# f1c200s_V1_0.net
KiCad netlist of a schematic drawn in EasyEDA Pro
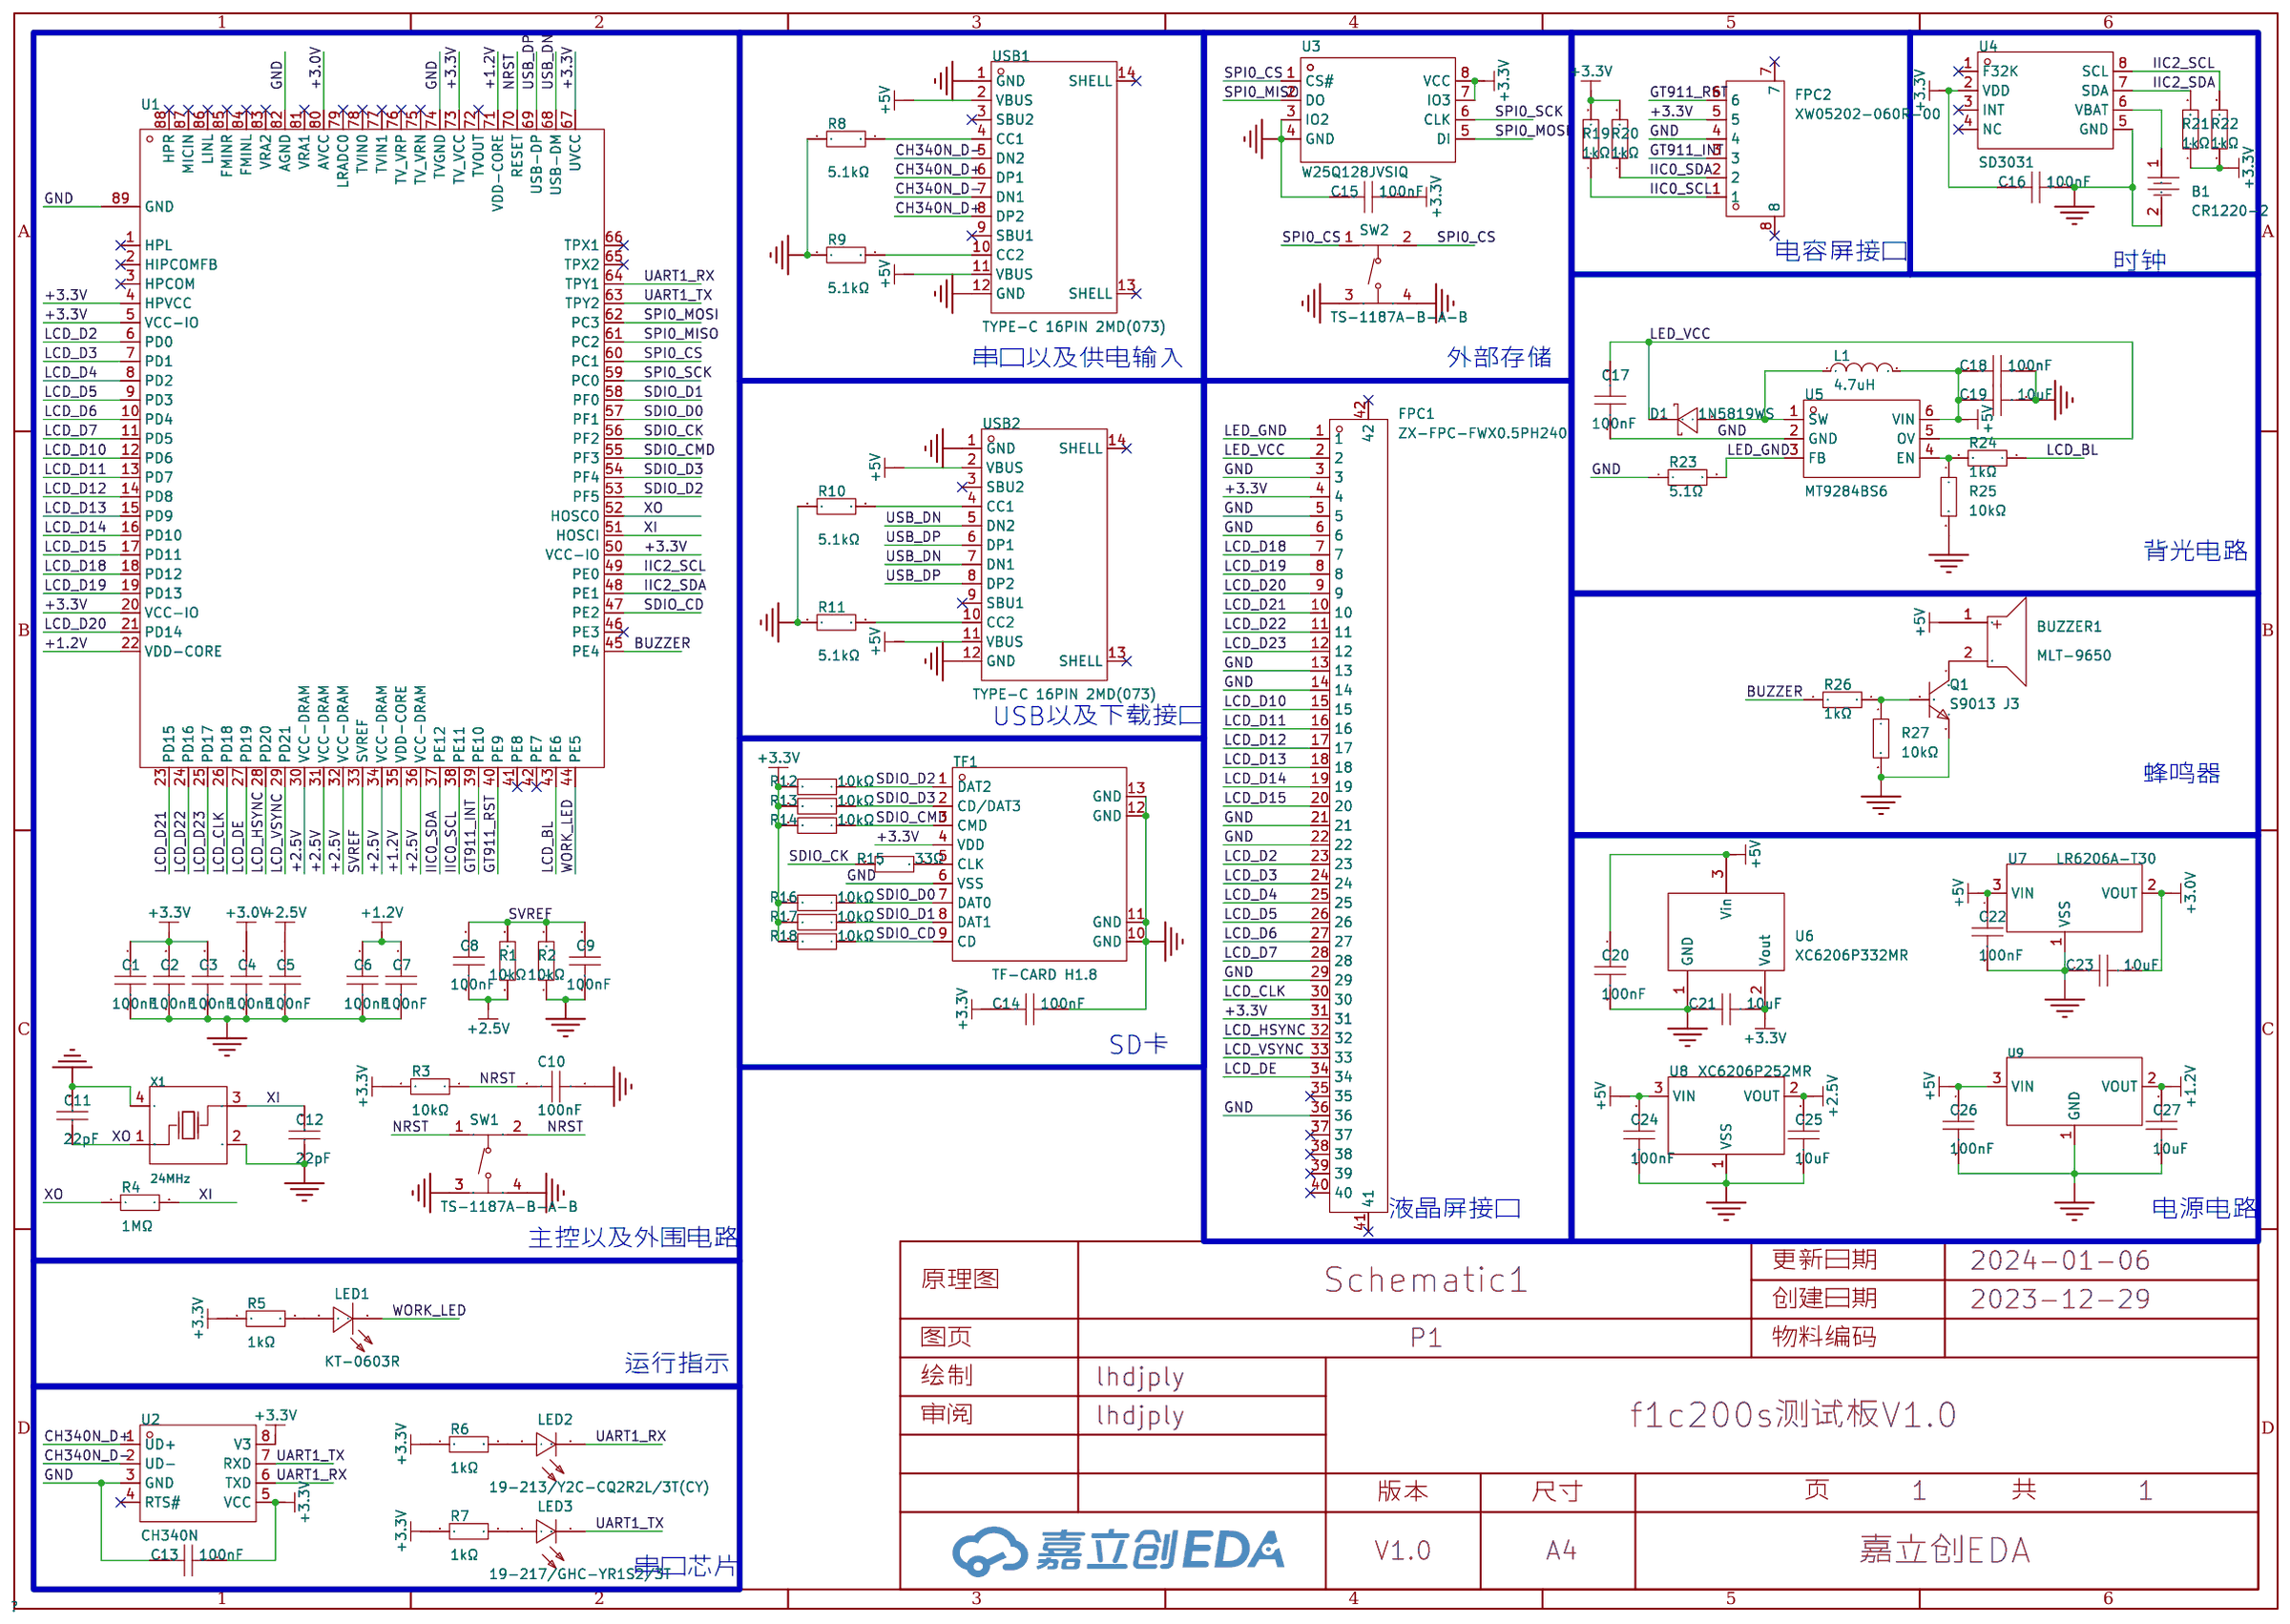
[diagram p0: schematic sheet]

(export (version "E")
  (design (tool "Eeschema 10.0.6"))
  (components
    (comp (ref "B1")
      (value "CR1220-2")
      (footprint "easyedapro:BAT-SMD_CR1220-2")
      (description "连接器类型:电池底座;适用电池规格:CR1220;工作温度范围:-;")
      (fields (field (name "Manufacturer") "Q&amp;J"))
      (libsource (lib "easyedapro") (part "CR1220-2"))
    )
    (comp (ref "BUZZER1")
      (value "2700Hz")
      (footprint "easyedapro:BUZ-SMD_L9.6-W9.6-LS10.0-R")
      (fields (field (name "Manufacturer Part") "MLT-9650") (field (name "Manufacturer") "华能"))
      (libsource (lib "easyedapro") (part "HND-9650B"))
    )
    (comp (ref "C1")
      (value "100nF")
      (footprint "easyedapro:C0603")
      (description "容值:100nF;精度:±10%;额定电压:50V;材质(温度系数):X7R;")
      (fields
        (field (name "Manufacturer Part") "CC0603KRX7R9BB104")
        (field (name "Manufacturer") "YAGEO(国巨)")
      )
      (libsource (lib "easyedapro") (part "CC0603KRX7R9BB104"))
    )
    (comp (ref "C2")
      (value "100nF")
      (footprint "easyedapro:C0603")
      (description "容值:100nF;精度:±10%;额定电压:50V;材质(温度系数):X7R;")
      (fields
        (field (name "Manufacturer Part") "CC0603KRX7R9BB104")
        (field (name "Manufacturer") "YAGEO(国巨)")
      )
      (libsource (lib "easyedapro") (part "CC0603KRX7R9BB104"))
    )
    (comp (ref "C3")
      (value "100nF")
      (footprint "easyedapro:C0603")
      (description "容值:100nF;精度:±10%;额定电压:50V;材质(温度系数):X7R;")
      (fields
        (field (name "Manufacturer Part") "CC0603KRX7R9BB104")
        (field (name "Manufacturer") "YAGEO(国巨)")
      )
      (libsource (lib "easyedapro") (part "CC0603KRX7R9BB104"))
    )
    (comp (ref "C4")
      (value "100nF")
      (footprint "easyedapro:C0603")
      (description "容值:100nF;精度:±10%;额定电压:50V;材质(温度系数):X7R;")
      (fields
        (field (name "Manufacturer Part") "CC0603KRX7R9BB104")
        (field (name "Manufacturer") "YAGEO(国巨)")
      )
      (libsource (lib "easyedapro") (part "CC0603KRX7R9BB104"))
    )
    (comp (ref "C5")
      (value "100nF")
      (footprint "easyedapro:C0603")
      (description "容值:100nF;精度:±10%;额定电压:50V;材质(温度系数):X7R;")
      (fields
        (field (name "Manufacturer Part") "CC0603KRX7R9BB104")
        (field (name "Manufacturer") "YAGEO(国巨)")
      )
      (libsource (lib "easyedapro") (part "CC0603KRX7R9BB104"))
    )
    (comp (ref "C6")
      (value "100nF")
      (footprint "easyedapro:C0603")
      (description "容值:100nF;精度:±10%;额定电压:50V;材质(温度系数):X7R;")
      (fields
        (field (name "Manufacturer Part") "CC0603KRX7R9BB104")
        (field (name "Manufacturer") "YAGEO(国巨)")
      )
      (libsource (lib "easyedapro") (part "CC0603KRX7R9BB104"))
    )
    (comp (ref "C7")
      (value "100nF")
      (footprint "easyedapro:C0603")
      (description "容值:100nF;精度:±10%;额定电压:50V;材质(温度系数):X7R;")
      (fields
        (field (name "Manufacturer Part") "CC0603KRX7R9BB104")
        (field (name "Manufacturer") "YAGEO(国巨)")
      )
      (libsource (lib "easyedapro") (part "CC0603KRX7R9BB104"))
    )
    (comp (ref "C8")
      (value "100nF")
      (footprint "easyedapro:C0603")
      (description "容值:100nF;精度:±10%;额定电压:50V;材质(温度系数):X7R;")
      (fields
        (field (name "Manufacturer Part") "CC0603KRX7R9BB104")
        (field (name "Manufacturer") "YAGEO(国巨)")
      )
      (libsource (lib "easyedapro") (part "CC0603KRX7R9BB104"))
    )
    (comp (ref "C9")
      (value "100nF")
      (footprint "easyedapro:C0603")
      (description "容值:100nF;精度:±10%;额定电压:50V;材质(温度系数):X7R;")
      (fields
        (field (name "Manufacturer Part") "CC0603KRX7R9BB104")
        (field (name "Manufacturer") "YAGEO(国巨)")
      )
      (libsource (lib "easyedapro") (part "CC0603KRX7R9BB104"))
    )
    (comp (ref "C10")
      (value "100nF")
      (footprint "easyedapro:C0603")
      (description "容值:100nF;精度:±10%;额定电压:50V;材质(温度系数):X7R;")
      (fields
        (field (name "Manufacturer Part") "CC0603KRX7R9BB104")
        (field (name "Manufacturer") "YAGEO(国巨)")
      )
      (libsource (lib "easyedapro") (part "CC0603KRX7R9BB104"))
    )
    (comp (ref "C11")
      (value "22pF")
      (footprint "easyedapro:C0603")
      (description "容值:22pF;精度:±5%;额定电压:50V;材质(温度系数):C0G;")
      (fields
        (field (name "Manufacturer Part") "CL10C220JB8NNNC")
        (field (name "Manufacturer") "SAMSUNG(三星)")
      )
      (libsource (lib "easyedapro") (part "CL10C220JB8NNNC"))
    )
    (comp (ref "C12")
      (value "22pF")
      (footprint "easyedapro:C0603")
      (description "容值:22pF;精度:±5%;额定电压:50V;材质(温度系数):C0G;")
      (fields
        (field (name "Manufacturer Part") "CL10C220JB8NNNC")
        (field (name "Manufacturer") "SAMSUNG(三星)")
      )
      (libsource (lib "easyedapro") (part "CL10C220JB8NNNC"))
    )
    (comp (ref "C13")
      (value "100nF")
      (footprint "easyedapro:C0603")
      (description "容值:100nF;精度:±10%;额定电压:50V;材质(温度系数):X7R;")
      (fields
        (field (name "Manufacturer Part") "CC0603KRX7R9BB104")
        (field (name "Manufacturer") "YAGEO(国巨)")
      )
      (libsource (lib "easyedapro") (part "CC0603KRX7R9BB104"))
    )
    (comp (ref "C14")
      (value "100nF")
      (footprint "easyedapro:C0603")
      (description "容值:100nF;精度:±10%;额定电压:50V;材质(温度系数):X7R;")
      (fields
        (field (name "Manufacturer Part") "CC0603KRX7R9BB104")
        (field (name "Manufacturer") "YAGEO(国巨)")
      )
      (libsource (lib "easyedapro") (part "CC0603KRX7R9BB104"))
    )
    (comp (ref "C15")
      (value "100nF")
      (footprint "easyedapro:C0603")
      (description "容值:100nF;精度:±10%;额定电压:50V;材质(温度系数):X7R;")
      (fields
        (field (name "Manufacturer Part") "CC0603KRX7R9BB104")
        (field (name "Manufacturer") "YAGEO(国巨)")
      )
      (libsource (lib "easyedapro") (part "CC0603KRX7R9BB104"))
    )
    (comp (ref "C16")
      (value "100nF")
      (footprint "easyedapro:C0603")
      (description "容值:100nF;精度:±10%;额定电压:50V;材质(温度系数):X7R;")
      (fields
        (field (name "Manufacturer Part") "CC0603KRX7R9BB104")
        (field (name "Manufacturer") "YAGEO(国巨)")
      )
      (libsource (lib "easyedapro") (part "CC0603KRX7R9BB104"))
    )
    (comp (ref "C17")
      (value "100nF")
      (footprint "easyedapro:C0603")
      (description "容值:100nF;精度:±10%;额定电压:50V;材质(温度系数):X7R;")
      (fields
        (field (name "Manufacturer Part") "CC0603KRX7R9BB104")
        (field (name "Manufacturer") "YAGEO(国巨)")
      )
      (libsource (lib "easyedapro") (part "CC0603KRX7R9BB104"))
    )
    (comp (ref "C18")
      (value "100nF")
      (footprint "easyedapro:C0603")
      (description "容值:100nF;精度:±10%;额定电压:50V;材质(温度系数):X7R;")
      (fields
        (field (name "Manufacturer Part") "CC0603KRX7R9BB104")
        (field (name "Manufacturer") "YAGEO(国巨)")
      )
      (libsource (lib "easyedapro") (part "CC0603KRX7R9BB104"))
    )
    (comp (ref "C19")
      (value "10uF")
      (footprint "easyedapro:C0603")
      (description "容值:10uF;精度:±10%;额定电压:10V;材质(温度系数):X5R;")
      (fields
        (field (name "Manufacturer Part") "CL10A106KP8NNNC")
        (field (name "Manufacturer") "SAMSUNG(三星)")
      )
      (libsource (lib "easyedapro") (part "CL10A106KP8NNNC"))
    )
    (comp (ref "C20")
      (value "100nF")
      (footprint "easyedapro:C0603")
      (description "容值:100nF;精度:±10%;额定电压:50V;材质(温度系数):X7R;")
      (fields
        (field (name "Manufacturer Part") "CC0603KRX7R9BB104")
        (field (name "Manufacturer") "YAGEO(国巨)")
      )
      (libsource (lib "easyedapro") (part "CC0603KRX7R9BB104"))
    )
    (comp (ref "C21")
      (value "10uF")
      (footprint "easyedapro:C0603")
      (description "容值:10uF;精度:±10%;额定电压:10V;材质(温度系数):X5R;")
      (fields
        (field (name "Manufacturer Part") "CL10A106KP8NNNC")
        (field (name "Manufacturer") "SAMSUNG(三星)")
      )
      (libsource (lib "easyedapro") (part "CL10A106KP8NNNC"))
    )
    (comp (ref "C22")
      (value "100nF")
      (footprint "easyedapro:C0603")
      (description "容值:100nF;精度:±10%;额定电压:50V;材质(温度系数):X7R;")
      (fields
        (field (name "Manufacturer Part") "CC0603KRX7R9BB104")
        (field (name "Manufacturer") "YAGEO(国巨)")
      )
      (libsource (lib "easyedapro") (part "CC0603KRX7R9BB104"))
    )
    (comp (ref "C23")
      (value "10uF")
      (footprint "easyedapro:C0603")
      (description "容值:10uF;精度:±10%;额定电压:10V;材质(温度系数):X5R;")
      (fields
        (field (name "Manufacturer Part") "CL10A106KP8NNNC")
        (field (name "Manufacturer") "SAMSUNG(三星)")
      )
      (libsource (lib "easyedapro") (part "CL10A106KP8NNNC"))
    )
    (comp (ref "C24")
      (value "100nF")
      (footprint "easyedapro:C0603")
      (description "容值:100nF;精度:±10%;额定电压:50V;材质(温度系数):X7R;")
      (fields
        (field (name "Manufacturer Part") "CC0603KRX7R9BB104")
        (field (name "Manufacturer") "YAGEO(国巨)")
      )
      (libsource (lib "easyedapro") (part "CC0603KRX7R9BB104"))
    )
    (comp (ref "C25")
      (value "10uF")
      (footprint "easyedapro:C0603")
      (description "容值:10uF;精度:±10%;额定电压:10V;材质(温度系数):X5R;")
      (fields
        (field (name "Manufacturer Part") "CL10A106KP8NNNC")
        (field (name "Manufacturer") "SAMSUNG(三星)")
      )
      (libsource (lib "easyedapro") (part "CL10A106KP8NNNC"))
    )
    (comp (ref "C26")
      (value "100nF")
      (footprint "easyedapro:C0603")
      (description "容值:100nF;精度:±10%;额定电压:50V;材质(温度系数):X7R;")
      (fields
        (field (name "Manufacturer Part") "CC0603KRX7R9BB104")
        (field (name "Manufacturer") "YAGEO(国巨)")
      )
      (libsource (lib "easyedapro") (part "CC0603KRX7R9BB104"))
    )
    (comp (ref "C27")
      (value "10uF")
      (footprint "easyedapro:C0603")
      (description "容值:10uF;精度:±10%;额定电压:10V;材质(温度系数):X5R;")
      (fields
        (field (name "Manufacturer Part") "CL10A106KP8NNNC")
        (field (name "Manufacturer") "SAMSUNG(三星)")
      )
      (libsource (lib "easyedapro") (part "CL10A106KP8NNNC"))
    )
    (comp (ref "D1")
      (value "1N5819WS")
      (footprint "easyedapro:SOD-323_L1.8-W1.3-LS2.5-RD")
      (description "正向压降(Vf):600mV@1A;直流反向耐压(Vr):40V;平均整流电流(Io):1A;")
      (fields (field (name "Manufacturer") "Hottech(合科泰)"))
      (libsource (lib "easyedapro") (part "1N5819WS"))
    )
    (comp (ref "FPC1")
      (value "ZX-FPC-FWX0.5PH240")
      (footprint "easyedapro:FPC-SMD_40P-P0.50_MEGASTAR_ZX-FPC-FWX0.5PH240")
      (description "间距:0.5mm;触点数量:40P;锁定特性:翻盖式;触点类型:下接;安装类型:卧贴;工作温度范围:-25°C~+85°C;焊接温度(最大值):260°C;")
      (fields (field (name "Manufacturer") "Megastar(兆星)"))
      (libsource (lib "easyedapro") (part "ZX-FPC-FWX0.5PH240"))
    )
    (comp (ref "FPC2")
      (value "XW05202-060R-00")
      (footprint "easyedapro:FPC-SMD_XW05202-060R-00")
      (description "间距:0.5mm;触点数量:6P;锁定特性:翻盖式;触点类型:下接;安装类型:卧贴;工作温度范围:-25°C~+85°C;")
      (fields (field (name "Manufacturer") "HCTL(华灿天禄)"))
      (libsource (lib "easyedapro") (part "XW05202-060R-00"))
    )
    (comp (ref "L1")
      (value "4.7uH")
      (footprint "easyedapro:IND-SMD_L5.8-W5.2_SLF05XX")
      (description "电感值:4.7uH;精度:±20%;额定电流:3A;饱和电流(Isat):3A;")
      (fields (field (name "Manufacturer Part") "CD54N-4R7M") (field (name "Manufacturer") "MINGSTAR(登壹)"))
      (libsource (lib "easyedapro") (part "CD54N-4R7M"))
    )
    (comp (ref "LED1")
      (value "KT-0603R")
      (footprint "easyedapro:LED0603-RD")
      (description "发光颜色:红灯;二极管配置:-;透镜颜色:-;主波长:-;色温:-;功率:-;发光角度:-;安装方式:-;工作温度:-40°C~+85°C;")
      (fields (field (name "Manufacturer") "KENTO"))
      (libsource (lib "easyedapro") (part "KT-0603R"))
    )
    (comp (ref "LED2")
      (value "19-213/Y2C-CQ2R2L/3T(CY)")
      (footprint "easyedapro:LED0603-RD-YELLOW")
      (description "发光颜色:黄灯;二极管配置:-;主波长:585.5nm~591.5nm;色温:-;功率:60mW;安装方式:-;")
      (fields (field (name "Manufacturer") "EVERLIGHT(亿光)"))
      (libsource (lib "easyedapro") (part "19-213/Y2C-CQ2R2L/3T(CY)"))
    )
    (comp (ref "LED3")
      (value "19-217/GHC-YR1S2/3T")
      (footprint "easyedapro:LED0603-RD")
      (fields (field (name "Manufacturer") "EVERLIGHT(亿光)"))
      (libsource (lib "easyedapro") (part "19-217/GHC-YR1S2/3T"))
    )
    (comp (ref "Q1")
      (value "S9013 J3")
      (footprint "easyedapro:SOT-23-3_L2.9-W1.3-P1.90-LS2.4-BR")
      (description "晶体管类型:NPN;集电极电流(Ic):500mA;集射极击穿电压(Vceo):25V;功率(Pd):300mW;直流电流增益(hFE@Ic,Vce):200@50mA,1V;")
      (fields (field (name "Manufacturer") "CJ(江苏长电/长晶)"))
      (libsource (lib "easyedapro") (part "S9013 J3"))
    )
    (comp (ref "R1")
      (value "10kΩ")
      (footprint "easyedapro:R0603")
      (description "阻值:10kΩ;精度:±1%;功率:100mW;温度系数:±100ppm/°C;电阻类型:厚膜电阻;")
      (fields
        (field (name "Manufacturer Part") "0603WAF1002T5E")
        (field (name "Manufacturer") "UNI-ROYAL(厚声)")
      )
      (libsource (lib "easyedapro") (part "0603WAF1002T5E"))
    )
    (comp (ref "R2")
      (value "10kΩ")
      (footprint "easyedapro:R0603")
      (description "阻值:10kΩ;精度:±1%;功率:100mW;温度系数:±100ppm/°C;电阻类型:厚膜电阻;")
      (fields
        (field (name "Manufacturer Part") "0603WAF1002T5E")
        (field (name "Manufacturer") "UNI-ROYAL(厚声)")
      )
      (libsource (lib "easyedapro") (part "0603WAF1002T5E"))
    )
    (comp (ref "R3")
      (value "10kΩ")
      (footprint "easyedapro:R0603")
      (description "阻值:10kΩ;精度:±1%;功率:100mW;温度系数:±100ppm/°C;电阻类型:厚膜电阻;")
      (fields
        (field (name "Manufacturer Part") "0603WAF1002T5E")
        (field (name "Manufacturer") "UNI-ROYAL(厚声)")
      )
      (libsource (lib "easyedapro") (part "0603WAF1002T5E"))
    )
    (comp (ref "R4")
      (value "1MΩ")
      (footprint "easyedapro:R0603")
      (description "阻值:1MΩ;精度:±1%;功率:100mW;温度系数:±100ppm/°C;电阻类型:厚膜电阻;")
      (fields
        (field (name "Manufacturer Part") "0603WAF1004T5E")
        (field (name "Manufacturer") "UNI-ROYAL(厚声)")
      )
      (libsource (lib "easyedapro") (part "0603WAF1004T5E"))
    )
    (comp (ref "R5")
      (value "1kΩ")
      (footprint "easyedapro:R0603")
      (description "阻值:1kΩ;精度:±1%;功率:100mW;温度系数:±100ppm/°C;电阻类型:厚膜电阻;")
      (fields
        (field (name "Manufacturer Part") "0603WAF1001T5E")
        (field (name "Manufacturer") "UNI-ROYAL(厚声)")
      )
      (libsource (lib "easyedapro") (part "0603WAF1001T5E"))
    )
    (comp (ref "R6")
      (value "1kΩ")
      (footprint "easyedapro:R0603")
      (description "阻值:1kΩ;精度:±1%;功率:100mW;温度系数:±100ppm/°C;电阻类型:厚膜电阻;")
      (fields
        (field (name "Manufacturer Part") "0603WAF1001T5E")
        (field (name "Manufacturer") "UNI-ROYAL(厚声)")
      )
      (libsource (lib "easyedapro") (part "0603WAF1001T5E"))
    )
    (comp (ref "R7")
      (value "1kΩ")
      (footprint "easyedapro:R0603")
      (description "阻值:1kΩ;精度:±1%;功率:100mW;温度系数:±100ppm/°C;电阻类型:厚膜电阻;")
      (fields
        (field (name "Manufacturer Part") "0603WAF1001T5E")
        (field (name "Manufacturer") "UNI-ROYAL(厚声)")
      )
      (libsource (lib "easyedapro") (part "0603WAF1001T5E"))
    )
    (comp (ref "R8")
      (value "5.1kΩ")
      (footprint "easyedapro:R0603")
      (description "阻值:5.1kΩ;精度:±1%;功率:100mW;温度系数:±100ppm/°C;电阻类型:厚膜电阻;")
      (fields
        (field (name "Manufacturer Part") "0603WAF5101T5E")
        (field (name "Manufacturer") "UNI-ROYAL(厚声)")
      )
      (libsource (lib "easyedapro") (part "0603WAF5101T5E"))
    )
    (comp (ref "R9")
      (value "5.1kΩ")
      (footprint "easyedapro:R0603")
      (description "阻值:5.1kΩ;精度:±1%;功率:100mW;温度系数:±100ppm/°C;电阻类型:厚膜电阻;")
      (fields
        (field (name "Manufacturer Part") "0603WAF5101T5E")
        (field (name "Manufacturer") "UNI-ROYAL(厚声)")
      )
      (libsource (lib "easyedapro") (part "0603WAF5101T5E"))
    )
    (comp (ref "R10")
      (value "5.1kΩ")
      (footprint "easyedapro:R0603")
      (description "阻值:5.1kΩ;精度:±1%;功率:100mW;温度系数:±100ppm/°C;电阻类型:厚膜电阻;")
      (fields
        (field (name "Manufacturer Part") "0603WAF5101T5E")
        (field (name "Manufacturer") "UNI-ROYAL(厚声)")
      )
      (libsource (lib "easyedapro") (part "0603WAF5101T5E"))
    )
    (comp (ref "R11")
      (value "5.1kΩ")
      (footprint "easyedapro:R0603")
      (description "阻值:5.1kΩ;精度:±1%;功率:100mW;温度系数:±100ppm/°C;电阻类型:厚膜电阻;")
      (fields
        (field (name "Manufacturer Part") "0603WAF5101T5E")
        (field (name "Manufacturer") "UNI-ROYAL(厚声)")
      )
      (libsource (lib "easyedapro") (part "0603WAF5101T5E"))
    )
    (comp (ref "R12")
      (value "10kΩ")
      (footprint "easyedapro:R0603")
      (description "阻值:10kΩ;精度:±1%;功率:100mW;温度系数:±100ppm/°C;电阻类型:厚膜电阻;")
      (fields
        (field (name "Manufacturer Part") "0603WAF1002T5E")
        (field (name "Manufacturer") "UNI-ROYAL(厚声)")
      )
      (libsource (lib "easyedapro") (part "0603WAF1002T5E"))
    )
    (comp (ref "R13")
      (value "10kΩ")
      (footprint "easyedapro:R0603")
      (description "阻值:10kΩ;精度:±1%;功率:100mW;温度系数:±100ppm/°C;电阻类型:厚膜电阻;")
      (fields
        (field (name "Manufacturer Part") "0603WAF1002T5E")
        (field (name "Manufacturer") "UNI-ROYAL(厚声)")
      )
      (libsource (lib "easyedapro") (part "0603WAF1002T5E"))
    )
    (comp (ref "R14")
      (value "10kΩ")
      (footprint "easyedapro:R0603")
      (description "阻值:10kΩ;精度:±1%;功率:100mW;温度系数:±100ppm/°C;电阻类型:厚膜电阻;")
      (fields
        (field (name "Manufacturer Part") "0603WAF1002T5E")
        (field (name "Manufacturer") "UNI-ROYAL(厚声)")
      )
      (libsource (lib "easyedapro") (part "0603WAF1002T5E"))
    )
    (comp (ref "R15")
      (value "33Ω")
      (footprint "easyedapro:R0603")
      (description "阻值:33Ω;精度:±1%;功率:100mW;温度系数:±100ppm/°C;电阻类型:厚膜电阻;")
      (fields
        (field (name "Manufacturer Part") "0603WAF330JT5E")
        (field (name "Manufacturer") "UNI-ROYAL(厚声)")
      )
      (libsource (lib "easyedapro") (part "0603WAF330JT5E"))
    )
    (comp (ref "R16")
      (value "10kΩ")
      (footprint "easyedapro:R0603")
      (description "阻值:10kΩ;精度:±1%;功率:100mW;温度系数:±100ppm/°C;电阻类型:厚膜电阻;")
      (fields
        (field (name "Manufacturer Part") "0603WAF1002T5E")
        (field (name "Manufacturer") "UNI-ROYAL(厚声)")
      )
      (libsource (lib "easyedapro") (part "0603WAF1002T5E"))
    )
    (comp (ref "R17")
      (value "10kΩ")
      (footprint "easyedapro:R0603")
      (description "阻值:10kΩ;精度:±1%;功率:100mW;温度系数:±100ppm/°C;电阻类型:厚膜电阻;")
      (fields
        (field (name "Manufacturer Part") "0603WAF1002T5E")
        (field (name "Manufacturer") "UNI-ROYAL(厚声)")
      )
      (libsource (lib "easyedapro") (part "0603WAF1002T5E"))
    )
    (comp (ref "R18")
      (value "10kΩ")
      (footprint "easyedapro:R0603")
      (description "阻值:10kΩ;精度:±1%;功率:100mW;温度系数:±100ppm/°C;电阻类型:厚膜电阻;")
      (fields
        (field (name "Manufacturer Part") "0603WAF1002T5E")
        (field (name "Manufacturer") "UNI-ROYAL(厚声)")
      )
      (libsource (lib "easyedapro") (part "0603WAF1002T5E"))
    )
    (comp (ref "R19")
      (value "1kΩ")
      (footprint "easyedapro:R0603")
      (description "阻值:1kΩ;精度:±1%;功率:100mW;温度系数:±100ppm/°C;电阻类型:厚膜电阻;")
      (fields
        (field (name "Manufacturer Part") "0603WAF1001T5E")
        (field (name "Manufacturer") "UNI-ROYAL(厚声)")
      )
      (libsource (lib "easyedapro") (part "0603WAF1001T5E"))
    )
    (comp (ref "R20")
      (value "1kΩ")
      (footprint "easyedapro:R0603")
      (description "阻值:1kΩ;精度:±1%;功率:100mW;温度系数:±100ppm/°C;电阻类型:厚膜电阻;")
      (fields
        (field (name "Manufacturer Part") "0603WAF1001T5E")
        (field (name "Manufacturer") "UNI-ROYAL(厚声)")
      )
      (libsource (lib "easyedapro") (part "0603WAF1001T5E"))
    )
    (comp (ref "R21")
      (value "1kΩ")
      (footprint "easyedapro:R0603")
      (description "阻值:1kΩ;精度:±1%;功率:100mW;温度系数:±100ppm/°C;电阻类型:厚膜电阻;")
      (fields
        (field (name "Manufacturer Part") "0603WAF1001T5E")
        (field (name "Manufacturer") "UNI-ROYAL(厚声)")
      )
      (libsource (lib "easyedapro") (part "0603WAF1001T5E"))
    )
    (comp (ref "R22")
      (value "1kΩ")
      (footprint "easyedapro:R0603")
      (description "阻值:1kΩ;精度:±1%;功率:100mW;温度系数:±100ppm/°C;电阻类型:厚膜电阻;")
      (fields
        (field (name "Manufacturer Part") "0603WAF1001T5E")
        (field (name "Manufacturer") "UNI-ROYAL(厚声)")
      )
      (libsource (lib "easyedapro") (part "0603WAF1001T5E"))
    )
    (comp (ref "R23")
      (value "5.1Ω")
      (footprint "easyedapro:R0603")
      (description "阻值:5.1Ω;精度:±1%;功率:100mW;温度系数:±200ppm/°C;电阻类型:厚膜电阻;")
      (fields
        (field (name "Manufacturer Part") "0603WAF510KT5E")
        (field (name "Manufacturer") "UNI-ROYAL(厚声)")
      )
      (libsource (lib "easyedapro") (part "0603WAF510KT5E"))
    )
    (comp (ref "R24")
      (value "1kΩ")
      (footprint "easyedapro:R0603")
      (description "阻值:1kΩ;精度:±1%;功率:100mW;温度系数:±100ppm/°C;电阻类型:厚膜电阻;")
      (fields
        (field (name "Manufacturer Part") "0603WAF1001T5E")
        (field (name "Manufacturer") "UNI-ROYAL(厚声)")
      )
      (libsource (lib "easyedapro") (part "0603WAF1001T5E"))
    )
    (comp (ref "R25")
      (value "10kΩ")
      (footprint "easyedapro:R0603")
      (description "阻值:10kΩ;精度:±1%;功率:100mW;温度系数:±100ppm/°C;电阻类型:厚膜电阻;")
      (fields
        (field (name "Manufacturer Part") "0603WAF1002T5E")
        (field (name "Manufacturer") "UNI-ROYAL(厚声)")
      )
      (libsource (lib "easyedapro") (part "0603WAF1002T5E"))
    )
    (comp (ref "R26")
      (value "1kΩ")
      (footprint "easyedapro:R0603")
      (description "阻值:1kΩ;精度:±1%;功率:100mW;温度系数:±100ppm/°C;电阻类型:厚膜电阻;")
      (fields
        (field (name "Manufacturer Part") "0603WAF1001T5E")
        (field (name "Manufacturer") "UNI-ROYAL(厚声)")
      )
      (libsource (lib "easyedapro") (part "0603WAF1001T5E"))
    )
    (comp (ref "R27")
      (value "10kΩ")
      (footprint "easyedapro:R0603")
      (description "阻值:10kΩ;精度:±1%;功率:100mW;温度系数:±100ppm/°C;电阻类型:厚膜电阻;")
      (fields
        (field (name "Manufacturer Part") "0603WAF1002T5E")
        (field (name "Manufacturer") "UNI-ROYAL(厚声)")
      )
      (libsource (lib "easyedapro") (part "0603WAF1002T5E"))
    )
    (comp (ref "SW1")
      (value "TS-1187A-B-A-B")
      (footprint "easyedapro:SW-SMD_4P-L5.1-W5.1-P3.70-LS6.5-TL-2")
      (description "触点电流:50mA;额定电压(DC):12V;绝缘电阻:-;电路结构:单刀单掷;安装方式:立贴;带灯:无;作用力:160gf;机械寿命:10万次;带支架:否;")
      (fields (field (name "Manufacturer") "XKB Connectivity(中国星坤)"))
      (libsource (lib "easyedapro") (part "TS-1187A-B-A-B"))
    )
    (comp (ref "SW2")
      (value "TS-1187A-B-A-B")
      (footprint "easyedapro:SW-SMD_4P-L5.1-W5.1-P3.70-LS6.5-TL-2")
      (description "触点电流:50mA;额定电压(DC):12V;绝缘电阻:-;电路结构:单刀单掷;安装方式:立贴;带灯:无;作用力:160gf;机械寿命:10万次;带支架:否;")
      (fields (field (name "Manufacturer") "XKB Connectivity(中国星坤)"))
      (libsource (lib "easyedapro") (part "TS-1187A-B-A-B"))
    )
    (comp (ref "TF1")
      (value "TF-CARD H1.8")
      (footprint "easyedapro:TF-SMD_TF-CARD-H1.8")
      (description "卡连接方式:自弹式;卡类型:MicroSD卡(TF卡);连接器类型:卡座;本体最大高度:1.8mm;触头材质:铜合金;触头镀层:金;工作温度范围:-40°C~+70°C;")
      (fields (field (name "Manufacturer") "SHOU HAN(首韩)"))
      (libsource (lib "easyedapro") (part "TF-CARD H1.8"))
    )
    (comp (ref "U1")
      (value "F1C200S")
      (footprint "easyedapro:QFN-88_L10.0-W10.0-P0.40-BL-EP6.75")
      (description "CPU内核:-;GPIO端口数量:-;工作电压范围:-;CPU最大主频:-;程序存储器类型:-;")
      (fields (field (name "Manufacturer") "Allwinner(全志)"))
      (libsource (lib "easyedapro") (part "F1C200S"))
    )
    (comp (ref "U2")
      (value "CH340N")
      (footprint "easyedapro:SOP-8_L4.9-W3.9-P1.27-LS6.0-BL")
      (fields (field (name "Manufacturer") "WCH(南京沁恒)"))
      (libsource (lib "easyedapro") (part "CH340N_C2977777"))
    )
    (comp (ref "U3")
      (value "W25Q128JVSIQ")
      (footprint "easyedapro:SOIC-8_L5.3-W5.3-P1.27-LS8.0-BL")
      (description "接口类型:-;存储容量:128Mbit;时钟频率(fc):-;")
      (fields (field (name "Manufacturer") "WINBOND(华邦)"))
      (libsource (lib "easyedapro") (part "W25Q128JVSIQTR"))
    )
    (comp (ref "U4")
      (value "SD3031")
      (footprint "easyedapro:SOP-8_L5.3-W5.3-P1.27-LS8.0-BL")
      (fields (field (name "Manufacturer") "WAVE(兴威帆电子)"))
      (libsource (lib "easyedapro") (part "SD3031"))
    )
    (comp (ref "U5")
      (value "MT9284BS6")
      (footprint "easyedapro:SOT-23-6_L2.9-W1.6-P0.95-LS2.8-BR")
      (fields (field (name "Manufacturer") "西安航天民芯"))
      (libsource (lib "easyedapro") (part "MT9284BS6"))
    )
    (comp (ref "U6")
      (value "XC6206P332MR")
      (footprint "easyedapro:SOT-23-3_L2.9-W1.6-P1.90-LS2.8-BR")
      (description "输出类型:固定;输出极性:正;最大输入电压:6V;输出电压:3.3V;输出电流:200mA;电源纹波抑制比(PSRR):-;")
      (fields (field (name "Manufacturer") "TOREX(特瑞仕)"))
      (libsource (lib "easyedapro") (part "XC6206P332MR"))
    )
    (comp (ref "U7")
      (value "LR6206A-T30")
      (footprint "easyedapro:SOT-23-3_L2.9-W1.3-P1.90-LS2.4-BR")
      (description "输出类型:固定;最大输入电压:6.5V;输出电压:3V;输出电流:300mA;电源纹波抑制比(PSRR):55dB@(1kHz);输出极性:正;")
      (fields (field (name "Manufacturer") "LR(朗瑞)"))
      (libsource (lib "easyedapro") (part "LR6206A-T30"))
    )
    (comp (ref "U8")
      (value "XC6206P252MR")
      (footprint "easyedapro:SOT-23-3_L2.9-W1.3-P1.90-LS2.4-BR")
      (description "输出类型:固定;最大输入电压:8V;输出电压:2.5V;输出电流:300mA;输出极性:正;")
      (fields (field (name "Manufacturer") "HXY MOSFET(华轩阳电子)"))
      (libsource (lib "easyedapro") (part "XC6206P252MR_C5148689"))
    )
    (comp (ref "U9")
      (value "LR8103A-T12")
      (footprint "easyedapro:SOT-23-3_L2.9-W1.6-P1.90-LS2.8-BR")
      (description "输出类型:-;最大输入电压:-;输出电压:1.2V;输出电流:300mA;电源纹波抑制比(PSRR):-;输出极性:-;")
      (fields (field (name "Manufacturer") "LR(朗瑞)"))
      (libsource (lib "easyedapro") (part "LR8103A-T12"))
    )
    (comp (ref "USB1")
      (value "TYPE-C 16PIN 2MD(073)")
      (footprint "easyedapro:USB-C-SMD_TYPE-C-6PIN-2MD-073")
      (description "连接器类型:Type-C;标准:-;公母:母;端口数量:1;触点数量:16P;安装方式:卧贴;额定电流 - 电源:5A;工作温度范围:-25°C~+85°C;")
      (fields (field (name "Manufacturer") "SHOU HAN(首韩)"))
      (libsource (lib "easyedapro") (part "TYPE-C 16PIN 2MD(073)"))
    )
    (comp (ref "USB2")
      (value "TYPE-C 16PIN 2MD(073)")
      (footprint "easyedapro:USB-C-SMD_TYPE-C-6PIN-2MD-073")
      (description "连接器类型:Type-C;标准:-;公母:母;端口数量:1;触点数量:16P;安装方式:卧贴;额定电流 - 电源:5A;工作温度范围:-25°C~+85°C;")
      (fields (field (name "Manufacturer") "SHOU HAN(首韩)"))
      (libsource (lib "easyedapro") (part "TYPE-C 16PIN 2MD(073)"))
    )
    (comp (ref "X1")
      (value "24MHz")
      (footprint "easyedapro:CRYSTAL-SMD_4P-L3.2-W2.5-BL-2")
      (description "频率:24MHz;频率公差:±10ppm;负载电容:20pF;")
      (fields (field (name "Manufacturer Part") "K3A240002010") (field (name "Manufacturer") "KYX(凯越翔电子)"))
      (libsource (lib "easyedapro") (part "K3A240002010"))
    )
  )
  (nets
    (net (code "1") (name "+1.2V") (class "Default")
      (node (ref "C27") (pin "2") (pinfunction "2_2") (pintype "unspecified"))
      (node (ref "C6") (pin "2") (pinfunction "2_2") (pintype "unspecified"))
      (node (ref "C7") (pin "2") (pinfunction "2_2") (pintype "unspecified"))
      (node (ref "U1") (pin "22") (pinfunction "VDD-CORE_22") (pintype "unspecified"))
      (node (ref "U1") (pin "35") (pinfunction "VDD-CORE_35") (pintype "unspecified"))
      (node (ref "U1") (pin "71") (pinfunction "VDD-CORE_71") (pintype "unspecified"))
      (node (ref "U9") (pin "2") (pinfunction "VOUT_2") (pintype "input"))
    )
    (net (code "2") (name "+2.5V") (class "Default")
      (node (ref "C25") (pin "2") (pinfunction "2_2") (pintype "unspecified"))
      (node (ref "C5") (pin "2") (pinfunction "2_2") (pintype "unspecified"))
      (node (ref "C8") (pin "1") (pinfunction "1_1") (pintype "unspecified"))
      (node (ref "R1") (pin "1") (pinfunction "1_1") (pintype "input"))
      (node (ref "U1") (pin "30") (pinfunction "VCC-DRAM_30") (pintype "unspecified"))
      (node (ref "U1") (pin "31") (pinfunction "VCC-DRAM_31") (pintype "unspecified"))
      (node (ref "U1") (pin "32") (pinfunction "VCC-DRAM_32") (pintype "unspecified"))
      (node (ref "U1") (pin "34") (pinfunction "VCC-DRAM_34") (pintype "unspecified"))
      (node (ref "U1") (pin "36") (pinfunction "VCC-DRAM_36") (pintype "unspecified"))
      (node (ref "U8") (pin "2") (pinfunction "VOUT_2") (pintype "unspecified"))
    )
    (net (code "3") (name "+3.0V") (class "Default")
      (node (ref "C23") (pin "2") (pinfunction "2_2") (pintype "unspecified"))
      (node (ref "C4") (pin "2") (pinfunction "2_2") (pintype "unspecified"))
      (node (ref "U1") (pin "80") (pinfunction "AVCC_80") (pintype "unspecified"))
      (node (ref "U7") (pin "2") (pinfunction "VOUT_2") (pintype "unspecified"))
    )
    (net (code "4") (name "+3.3V") (class "Default")
      (node (ref "C1") (pin "2") (pinfunction "2_2") (pintype "unspecified"))
      (node (ref "C13") (pin "1") (pinfunction "1_1") (pintype "unspecified"))
      (node (ref "C14") (pin "2") (pinfunction "2_2") (pintype "unspecified"))
      (node (ref "C15") (pin "1") (pinfunction "1_1") (pintype "unspecified"))
      (node (ref "C16") (pin "2") (pinfunction "2_2") (pintype "unspecified"))
      (node (ref "C2") (pin "2") (pinfunction "2_2") (pintype "unspecified"))
      (node (ref "C21") (pin "2") (pinfunction "2_2") (pintype "unspecified"))
      (node (ref "C3") (pin "2") (pinfunction "2_2") (pintype "unspecified"))
      (node (ref "FPC1") (pin "31") (pinfunction "31_31") (pintype "unspecified"))
      (node (ref "FPC1") (pin "4") (pinfunction "4_4") (pintype "unspecified"))
      (node (ref "FPC2") (pin "5") (pinfunction "5_5") (pintype "unspecified"))
      (node (ref "R12") (pin "2") (pinfunction "2_2") (pintype "input"))
      (node (ref "R13") (pin "2") (pinfunction "2_2") (pintype "input"))
      (node (ref "R14") (pin "2") (pinfunction "2_2") (pintype "input"))
      (node (ref "R16") (pin "2") (pinfunction "2_2") (pintype "input"))
      (node (ref "R17") (pin "2") (pinfunction "2_2") (pintype "input"))
      (node (ref "R18") (pin "2") (pinfunction "2_2") (pintype "input"))
      (node (ref "R19") (pin "2") (pinfunction "2_2") (pintype "input"))
      (node (ref "R20") (pin "2") (pinfunction "2_2") (pintype "input"))
      (node (ref "R21") (pin "1") (pinfunction "1_1") (pintype "input"))
      (node (ref "R22") (pin "1") (pinfunction "1_1") (pintype "input"))
      (node (ref "R3") (pin "2") (pinfunction "2_2") (pintype "input"))
      (node (ref "R5") (pin "1") (pinfunction "1_1") (pintype "input"))
      (node (ref "R6") (pin "1") (pinfunction "1_1") (pintype "input"))
      (node (ref "R7") (pin "1") (pinfunction "1_1") (pintype "input"))
      (node (ref "TF1") (pin "4") (pinfunction "VDD_4") (pintype "unspecified"))
      (node (ref "U1") (pin "20") (pinfunction "VCC-IO_20") (pintype "unspecified"))
      (node (ref "U1") (pin "4") (pinfunction "HPVCC_4") (pintype "unspecified"))
      (node (ref "U1") (pin "5") (pinfunction "VCC-IO_5") (pintype "unspecified"))
      (node (ref "U1") (pin "50") (pinfunction "VCC-IO_50") (pintype "unspecified"))
      (node (ref "U1") (pin "67") (pinfunction "UVCC_67") (pintype "unspecified"))
      (node (ref "U1") (pin "73") (pinfunction "TV_VCC_73") (pintype "unspecified"))
      (node (ref "U2") (pin "5") (pinfunction "VCC_5") (pintype "unspecified"))
      (node (ref "U2") (pin "8") (pinfunction "V3_8") (pintype "unspecified"))
      (node (ref "U3") (pin "7") (pinfunction "IO3_7") (pintype "unspecified"))
      (node (ref "U3") (pin "8") (pinfunction "VCC_8") (pintype "unspecified"))
      (node (ref "U4") (pin "2") (pinfunction "VDD_2") (pintype "input"))
      (node (ref "U6") (pin "2") (pinfunction "Vout_2") (pintype "input"))
    )
    (net (code "5") (name "+5V") (class "Default")
      (node (ref "BUZZER1") (pin "1") (pinfunction "1_1") (pintype "input"))
      (node (ref "C18") (pin "2") (pinfunction "2_2") (pintype "unspecified"))
      (node (ref "C19") (pin "1") (pinfunction "1_1") (pintype "unspecified"))
      (node (ref "C20") (pin "1") (pinfunction "1_1") (pintype "unspecified"))
      (node (ref "C22") (pin "1") (pinfunction "1_1") (pintype "unspecified"))
      (node (ref "C24") (pin "1") (pinfunction "1_1") (pintype "unspecified"))
      (node (ref "C26") (pin "1") (pinfunction "1_1") (pintype "unspecified"))
      (node (ref "L1") (pin "2") (pinfunction "2_2") (pintype "input"))
      (node (ref "U5") (pin "6") (pinfunction "VIN_6") (pintype "input"))
      (node (ref "U6") (pin "3") (pinfunction "Vin_3") (pintype "input"))
      (node (ref "U7") (pin "3") (pinfunction "VIN_3") (pintype "unspecified"))
      (node (ref "U8") (pin "3") (pinfunction "VIN_3") (pintype "unspecified"))
      (node (ref "U9") (pin "3") (pinfunction "VIN_3") (pintype "input"))
      (node (ref "USB1") (pin "11") (pinfunction "VBUS_11") (pintype "unspecified"))
      (node (ref "USB1") (pin "2") (pinfunction "VBUS_2") (pintype "unspecified"))
      (node (ref "USB2") (pin "11") (pinfunction "VBUS_11") (pintype "unspecified"))
      (node (ref "USB2") (pin "2") (pinfunction "VBUS_2") (pintype "unspecified"))
    )
    (net (code "6") (name "/BUZZER") (class "Default")
      (node (ref "R26") (pin "2") (pinfunction "2_2") (pintype "input"))
      (node (ref "U1") (pin "45") (pinfunction "PE4_45") (pintype "unspecified"))
    )
    (net (code "7") (name "/CH340N_D+") (class "Default")
      (node (ref "U2") (pin "1") (pinfunction "UD+_1") (pintype "unspecified"))
      (node (ref "USB1") (pin "6") (pinfunction "DP1_6") (pintype "unspecified"))
      (node (ref "USB1") (pin "8") (pinfunction "DP2_8") (pintype "unspecified"))
    )
    (net (code "8") (name "/CH340N_D-") (class "Default")
      (node (ref "U2") (pin "2") (pinfunction "UD-_2") (pintype "unspecified"))
      (node (ref "USB1") (pin "5") (pinfunction "DN2_5") (pintype "unspecified"))
      (node (ref "USB1") (pin "7") (pinfunction "DN1_7") (pintype "unspecified"))
    )
    (net (code "9") (name "/GT911_INT") (class "Default")
      (node (ref "FPC2") (pin "3") (pinfunction "3_3") (pintype "unspecified"))
      (node (ref "U1") (pin "39") (pinfunction "PE10_39") (pintype "unspecified"))
    )
    (net (code "10") (name "/GT911_RST") (class "Default")
      (node (ref "FPC2") (pin "6") (pinfunction "6_6") (pintype "unspecified"))
      (node (ref "U1") (pin "40") (pinfunction "PE9_40") (pintype "unspecified"))
    )
    (net (code "11") (name "/IIC0_SCL") (class "Default")
      (node (ref "FPC2") (pin "1") (pinfunction "1_1") (pintype "unspecified"))
      (node (ref "R19") (pin "1") (pinfunction "1_1") (pintype "input"))
      (node (ref "U1") (pin "38") (pinfunction "PE11_38") (pintype "unspecified"))
    )
    (net (code "12") (name "/IIC0_SDA") (class "Default")
      (node (ref "FPC2") (pin "2") (pinfunction "2_2") (pintype "unspecified"))
      (node (ref "R20") (pin "1") (pinfunction "1_1") (pintype "input"))
      (node (ref "U1") (pin "37") (pinfunction "PE12_37") (pintype "unspecified"))
    )
    (net (code "13") (name "/IIC2_SCL") (class "Default")
      (node (ref "R22") (pin "2") (pinfunction "2_2") (pintype "input"))
      (node (ref "U1") (pin "49") (pinfunction "PE0_49") (pintype "unspecified"))
      (node (ref "U4") (pin "8") (pinfunction "SCL_8") (pintype "input"))
    )
    (net (code "14") (name "/IIC2_SDA") (class "Default")
      (node (ref "R21") (pin "2") (pinfunction "2_2") (pintype "input"))
      (node (ref "U1") (pin "48") (pinfunction "PE1_48") (pintype "unspecified"))
      (node (ref "U4") (pin "7") (pinfunction "SDA_7") (pintype "input"))
    )
    (net (code "15") (name "/LCD_BL") (class "Default")
      (node (ref "R24") (pin "1") (pinfunction "1_1") (pintype "input"))
      (node (ref "U1") (pin "43") (pinfunction "PE6_43") (pintype "unspecified"))
    )
    (net (code "16") (name "/LCD_CLK") (class "Default")
      (node (ref "FPC1") (pin "30") (pinfunction "30_30") (pintype "unspecified"))
      (node (ref "U1") (pin "26") (pinfunction "PD18_26") (pintype "unspecified"))
    )
    (net (code "17") (name "/LCD_D2") (class "Default")
      (node (ref "FPC1") (pin "23") (pinfunction "23_23") (pintype "unspecified"))
      (node (ref "U1") (pin "6") (pinfunction "PD0_6") (pintype "unspecified"))
    )
    (net (code "18") (name "/LCD_D3") (class "Default")
      (node (ref "FPC1") (pin "24") (pinfunction "24_24") (pintype "unspecified"))
      (node (ref "U1") (pin "7") (pinfunction "PD1_7") (pintype "unspecified"))
    )
    (net (code "19") (name "/LCD_D4") (class "Default")
      (node (ref "FPC1") (pin "25") (pinfunction "25_25") (pintype "unspecified"))
      (node (ref "U1") (pin "8") (pinfunction "PD2_8") (pintype "unspecified"))
    )
    (net (code "20") (name "/LCD_D5") (class "Default")
      (node (ref "FPC1") (pin "26") (pinfunction "26_26") (pintype "unspecified"))
      (node (ref "U1") (pin "9") (pinfunction "PD3_9") (pintype "unspecified"))
    )
    (net (code "21") (name "/LCD_D6") (class "Default")
      (node (ref "FPC1") (pin "27") (pinfunction "27_27") (pintype "unspecified"))
      (node (ref "U1") (pin "10") (pinfunction "PD4_10") (pintype "unspecified"))
    )
    (net (code "22") (name "/LCD_D7") (class "Default")
      (node (ref "FPC1") (pin "28") (pinfunction "28_28") (pintype "unspecified"))
      (node (ref "U1") (pin "11") (pinfunction "PD5_11") (pintype "unspecified"))
    )
    (net (code "23") (name "/LCD_D10") (class "Default")
      (node (ref "FPC1") (pin "15") (pinfunction "15_15") (pintype "unspecified"))
      (node (ref "U1") (pin "12") (pinfunction "PD6_12") (pintype "unspecified"))
    )
    (net (code "24") (name "/LCD_D11") (class "Default")
      (node (ref "FPC1") (pin "16") (pinfunction "16_16") (pintype "unspecified"))
      (node (ref "U1") (pin "13") (pinfunction "PD7_13") (pintype "unspecified"))
    )
    (net (code "25") (name "/LCD_D12") (class "Default")
      (node (ref "FPC1") (pin "17") (pinfunction "17_17") (pintype "unspecified"))
      (node (ref "U1") (pin "14") (pinfunction "PD8_14") (pintype "unspecified"))
    )
    (net (code "26") (name "/LCD_D13") (class "Default")
      (node (ref "FPC1") (pin "18") (pinfunction "18_18") (pintype "unspecified"))
      (node (ref "U1") (pin "15") (pinfunction "PD9_15") (pintype "unspecified"))
    )
    (net (code "27") (name "/LCD_D14") (class "Default")
      (node (ref "FPC1") (pin "19") (pinfunction "19_19") (pintype "unspecified"))
      (node (ref "U1") (pin "16") (pinfunction "PD10_16") (pintype "unspecified"))
    )
    (net (code "28") (name "/LCD_D15") (class "Default")
      (node (ref "FPC1") (pin "20") (pinfunction "20_20") (pintype "unspecified"))
      (node (ref "U1") (pin "17") (pinfunction "PD11_17") (pintype "unspecified"))
    )
    (net (code "29") (name "/LCD_D18") (class "Default")
      (node (ref "FPC1") (pin "7") (pinfunction "7_7") (pintype "unspecified"))
      (node (ref "U1") (pin "18") (pinfunction "PD12_18") (pintype "unspecified"))
    )
    (net (code "30") (name "/LCD_D19") (class "Default")
      (node (ref "FPC1") (pin "8") (pinfunction "8_8") (pintype "unspecified"))
      (node (ref "U1") (pin "19") (pinfunction "PD13_19") (pintype "unspecified"))
    )
    (net (code "31") (name "/LCD_D20") (class "Default")
      (node (ref "FPC1") (pin "9") (pinfunction "9_9") (pintype "unspecified"))
      (node (ref "U1") (pin "21") (pinfunction "PD14_21") (pintype "unspecified"))
    )
    (net (code "32") (name "/LCD_D21") (class "Default")
      (node (ref "FPC1") (pin "10") (pinfunction "10_10") (pintype "unspecified"))
      (node (ref "U1") (pin "23") (pinfunction "PD15_23") (pintype "unspecified"))
    )
    (net (code "33") (name "/LCD_D22") (class "Default")
      (node (ref "FPC1") (pin "11") (pinfunction "11_11") (pintype "unspecified"))
      (node (ref "U1") (pin "24") (pinfunction "PD16_24") (pintype "unspecified"))
    )
    (net (code "34") (name "/LCD_D23") (class "Default")
      (node (ref "FPC1") (pin "12") (pinfunction "12_12") (pintype "unspecified"))
      (node (ref "U1") (pin "25") (pinfunction "PD17_25") (pintype "unspecified"))
    )
    (net (code "35") (name "/LCD_DE") (class "Default")
      (node (ref "FPC1") (pin "34") (pinfunction "34_34") (pintype "unspecified"))
      (node (ref "U1") (pin "27") (pinfunction "PD19_27") (pintype "unspecified"))
    )
    (net (code "36") (name "/LCD_HSYNC") (class "Default")
      (node (ref "FPC1") (pin "32") (pinfunction "32_32") (pintype "unspecified"))
      (node (ref "U1") (pin "28") (pinfunction "PD20_28") (pintype "unspecified"))
    )
    (net (code "37") (name "/LCD_VSYNC") (class "Default")
      (node (ref "FPC1") (pin "33") (pinfunction "33_33") (pintype "unspecified"))
      (node (ref "U1") (pin "29") (pinfunction "PD21_29") (pintype "unspecified"))
    )
    (net (code "38") (name "/LED_GND") (class "Default")
      (node (ref "FPC1") (pin "1") (pinfunction "1_1") (pintype "unspecified"))
      (node (ref "R23") (pin "2") (pinfunction "2_2") (pintype "input"))
      (node (ref "U5") (pin "3") (pinfunction "FB_3") (pintype "input"))
    )
    (net (code "39") (name "/LED_VCC") (class "Default")
      (node (ref "C17") (pin "2") (pinfunction "2_2") (pintype "unspecified"))
      (node (ref "D1") (pin "1") (pinfunction "K_1") (pintype "unspecified"))
      (node (ref "FPC1") (pin "2") (pinfunction "2_2") (pintype "unspecified"))
      (node (ref "U5") (pin "5") (pinfunction "OV_5") (pintype "input"))
    )
    (net (code "40") (name "/NRST") (class "Default")
      (node (ref "C10") (pin "2") (pinfunction "2_2") (pintype "unspecified"))
      (node (ref "R3") (pin "1") (pinfunction "1_1") (pintype "input"))
      (node (ref "SW1") (pin "1") (pinfunction "A_1") (pintype "unspecified"))
      (node (ref "SW1") (pin "2") (pinfunction "B_2") (pintype "unspecified"))
      (node (ref "U1") (pin "70") (pinfunction "RESET_70") (pintype "unspecified"))
    )
    (net (code "41") (name "/SDIO_CD") (class "Default")
      (node (ref "R18") (pin "1") (pinfunction "1_1") (pintype "input"))
      (node (ref "TF1") (pin "9") (pinfunction "CD_9") (pintype "unspecified"))
      (node (ref "U1") (pin "47") (pinfunction "PE2_47") (pintype "unspecified"))
    )
    (net (code "42") (name "/SDIO_CK") (class "Default")
      (node (ref "R15") (pin "1") (pinfunction "1_1") (pintype "input"))
      (node (ref "U1") (pin "56") (pinfunction "PF2_56") (pintype "unspecified"))
    )
    (net (code "43") (name "/SDIO_CMD") (class "Default")
      (node (ref "R14") (pin "1") (pinfunction "1_1") (pintype "input"))
      (node (ref "TF1") (pin "3") (pinfunction "CMD_3") (pintype "unspecified"))
      (node (ref "U1") (pin "55") (pinfunction "PF3_55") (pintype "unspecified"))
    )
    (net (code "44") (name "/SDIO_D0") (class "Default")
      (node (ref "R16") (pin "1") (pinfunction "1_1") (pintype "input"))
      (node (ref "TF1") (pin "7") (pinfunction "DAT0_7") (pintype "unspecified"))
      (node (ref "U1") (pin "57") (pinfunction "PF1_57") (pintype "unspecified"))
    )
    (net (code "45") (name "/SDIO_D1") (class "Default")
      (node (ref "R17") (pin "1") (pinfunction "1_1") (pintype "input"))
      (node (ref "TF1") (pin "8") (pinfunction "DAT1_8") (pintype "unspecified"))
      (node (ref "U1") (pin "58") (pinfunction "PF0_58") (pintype "unspecified"))
    )
    (net (code "46") (name "/SDIO_D2") (class "Default")
      (node (ref "R12") (pin "1") (pinfunction "1_1") (pintype "input"))
      (node (ref "TF1") (pin "1") (pinfunction "DAT2_1") (pintype "unspecified"))
      (node (ref "U1") (pin "53") (pinfunction "PF5_53") (pintype "unspecified"))
    )
    (net (code "47") (name "/SDIO_D3") (class "Default")
      (node (ref "R13") (pin "1") (pinfunction "1_1") (pintype "input"))
      (node (ref "TF1") (pin "2") (pinfunction "CD/DAT3_2") (pintype "unspecified"))
      (node (ref "U1") (pin "54") (pinfunction "PF4_54") (pintype "unspecified"))
    )
    (net (code "48") (name "/SPI0_CS") (class "Default")
      (node (ref "SW2") (pin "1") (pinfunction "A_1") (pintype "unspecified"))
      (node (ref "SW2") (pin "2") (pinfunction "B_2") (pintype "unspecified"))
      (node (ref "U1") (pin "60") (pinfunction "PC1_60") (pintype "unspecified"))
      (node (ref "U3") (pin "1") (pinfunction "CS#_1") (pintype "unspecified"))
    )
    (net (code "49") (name "/SPI0_MISO") (class "Default")
      (node (ref "U1") (pin "61") (pinfunction "PC2_61") (pintype "unspecified"))
      (node (ref "U3") (pin "2") (pinfunction "DO_2") (pintype "unspecified"))
    )
    (net (code "50") (name "/SPI0_MOSI") (class "Default")
      (node (ref "U1") (pin "62") (pinfunction "PC3_62") (pintype "unspecified"))
      (node (ref "U3") (pin "5") (pinfunction "DI_5") (pintype "unspecified"))
    )
    (net (code "51") (name "/SPI0_SCK") (class "Default")
      (node (ref "U1") (pin "59") (pinfunction "PC0_59") (pintype "unspecified"))
      (node (ref "U3") (pin "6") (pinfunction "CLK_6") (pintype "unspecified"))
    )
    (net (code "52") (name "/SVREF") (class "Default")
      (node (ref "C8") (pin "2") (pinfunction "2_2") (pintype "unspecified"))
      (node (ref "C9") (pin "2") (pinfunction "2_2") (pintype "unspecified"))
      (node (ref "R1") (pin "2") (pinfunction "2_2") (pintype "input"))
      (node (ref "R2") (pin "2") (pinfunction "2_2") (pintype "input"))
      (node (ref "U1") (pin "33") (pinfunction "SVREF_33") (pintype "unspecified"))
    )
    (net (code "53") (name "/UART1_RX") (class "Default")
      (node (ref "LED2") (pin "1") (pinfunction "C_1") (pintype "input"))
      (node (ref "U1") (pin "64") (pinfunction "TPY1_64") (pintype "unspecified"))
      (node (ref "U2") (pin "6") (pinfunction "TXD_6") (pintype "unspecified"))
    )
    (net (code "54") (name "/UART1_TX") (class "Default")
      (node (ref "LED3") (pin "1") (pinfunction "C_1") (pintype "input"))
      (node (ref "U1") (pin "63") (pinfunction "TPY2_63") (pintype "unspecified"))
      (node (ref "U2") (pin "7") (pinfunction "RXD_7") (pintype "unspecified"))
    )
    (net (code "55") (name "/USB_DN") (class "Default")
      (node (ref "U1") (pin "68") (pinfunction "USB-DM_68") (pintype "unspecified"))
      (node (ref "USB2") (pin "5") (pinfunction "DN2_5") (pintype "unspecified"))
      (node (ref "USB2") (pin "7") (pinfunction "DN1_7") (pintype "unspecified"))
    )
    (net (code "56") (name "/USB_DP") (class "Default")
      (node (ref "U1") (pin "69") (pinfunction "USB-DP_69") (pintype "unspecified"))
      (node (ref "USB2") (pin "6") (pinfunction "DP1_6") (pintype "unspecified"))
      (node (ref "USB2") (pin "8") (pinfunction "DP2_8") (pintype "unspecified"))
    )
    (net (code "57") (name "/WORK_LED") (class "Default")
      (node (ref "LED1") (pin "1") (pinfunction "K_1") (pintype "input"))
      (node (ref "U1") (pin "44") (pinfunction "PE5_44") (pintype "unspecified"))
    )
    (net (code "58") (name "/XI") (class "Default")
      (node (ref "C12") (pin "2") (pinfunction "2_2") (pintype "input"))
      (node (ref "R4") (pin "2") (pinfunction "2_2") (pintype "input"))
      (node (ref "U1") (pin "51") (pinfunction "HOSCI_51") (pintype "unspecified"))
      (node (ref "X1") (pin "3") (pinfunction "OSC2_3") (pintype "input"))
    )
    (net (code "59") (name "/XO") (class "Default")
      (node (ref "C11") (pin "1") (pinfunction "1_1") (pintype "input"))
      (node (ref "R4") (pin "1") (pinfunction "1_1") (pintype "input"))
      (node (ref "U1") (pin "52") (pinfunction "HOSCO_52") (pintype "unspecified"))
      (node (ref "X1") (pin "1") (pinfunction "OSC1_1") (pintype "input"))
    )
    (net (code "60") (name "GND") (class "Default")
      (node (ref "B1") (pin "2") (pinfunction "2_2") (pintype "input"))
      (node (ref "C1") (pin "1") (pinfunction "1_1") (pintype "unspecified"))
      (node (ref "C10") (pin "1") (pinfunction "1_1") (pintype "unspecified"))
      (node (ref "C11") (pin "2") (pinfunction "2_2") (pintype "input"))
      (node (ref "C12") (pin "1") (pinfunction "1_1") (pintype "input"))
      (node (ref "C13") (pin "2") (pinfunction "2_2") (pintype "unspecified"))
      (node (ref "C14") (pin "1") (pinfunction "1_1") (pintype "unspecified"))
      (node (ref "C15") (pin "2") (pinfunction "2_2") (pintype "unspecified"))
      (node (ref "C16") (pin "1") (pinfunction "1_1") (pintype "unspecified"))
      (node (ref "C17") (pin "1") (pinfunction "1_1") (pintype "unspecified"))
      (node (ref "C18") (pin "1") (pinfunction "1_1") (pintype "unspecified"))
      (node (ref "C19") (pin "2") (pinfunction "2_2") (pintype "unspecified"))
      (node (ref "C2") (pin "1") (pinfunction "1_1") (pintype "unspecified"))
      (node (ref "C20") (pin "2") (pinfunction "2_2") (pintype "unspecified"))
      (node (ref "C21") (pin "1") (pinfunction "1_1") (pintype "unspecified"))
      (node (ref "C22") (pin "2") (pinfunction "2_2") (pintype "unspecified"))
      (node (ref "C23") (pin "1") (pinfunction "1_1") (pintype "unspecified"))
      (node (ref "C24") (pin "2") (pinfunction "2_2") (pintype "unspecified"))
      (node (ref "C25") (pin "1") (pinfunction "1_1") (pintype "unspecified"))
      (node (ref "C26") (pin "2") (pinfunction "2_2") (pintype "unspecified"))
      (node (ref "C27") (pin "1") (pinfunction "1_1") (pintype "unspecified"))
      (node (ref "C3") (pin "1") (pinfunction "1_1") (pintype "unspecified"))
      (node (ref "C4") (pin "1") (pinfunction "1_1") (pintype "unspecified"))
      (node (ref "C5") (pin "1") (pinfunction "1_1") (pintype "unspecified"))
      (node (ref "C6") (pin "1") (pinfunction "1_1") (pintype "unspecified"))
      (node (ref "C7") (pin "1") (pinfunction "1_1") (pintype "unspecified"))
      (node (ref "C9") (pin "1") (pinfunction "1_1") (pintype "unspecified"))
      (node (ref "FPC1") (pin "13") (pinfunction "13_13") (pintype "unspecified"))
      (node (ref "FPC1") (pin "14") (pinfunction "14_14") (pintype "unspecified"))
      (node (ref "FPC1") (pin "21") (pinfunction "21_21") (pintype "unspecified"))
      (node (ref "FPC1") (pin "22") (pinfunction "22_22") (pintype "unspecified"))
      (node (ref "FPC1") (pin "29") (pinfunction "29_29") (pintype "unspecified"))
      (node (ref "FPC1") (pin "3") (pinfunction "3_3") (pintype "unspecified"))
      (node (ref "FPC1") (pin "36") (pinfunction "36_36") (pintype "unspecified"))
      (node (ref "FPC1") (pin "5") (pinfunction "5_5") (pintype "unspecified"))
      (node (ref "FPC1") (pin "6") (pinfunction "6_6") (pintype "unspecified"))
      (node (ref "FPC2") (pin "4") (pinfunction "4_4") (pintype "unspecified"))
      (node (ref "Q1") (pin "2") (pinfunction "E_2") (pintype "unspecified"))
      (node (ref "R10") (pin "1") (pinfunction "1_1") (pintype "input"))
      (node (ref "R11") (pin "1") (pinfunction "1_1") (pintype "input"))
      (node (ref "R2") (pin "1") (pinfunction "1_1") (pintype "input"))
      (node (ref "R23") (pin "1") (pinfunction "1_1") (pintype "input"))
      (node (ref "R25") (pin "2") (pinfunction "2_2") (pintype "input"))
      (node (ref "R27") (pin "2") (pinfunction "2_2") (pintype "input"))
      (node (ref "R8") (pin "1") (pinfunction "1_1") (pintype "input"))
      (node (ref "R9") (pin "1") (pinfunction "1_1") (pintype "input"))
      (node (ref "SW1") (pin "3") (pinfunction "C_3") (pintype "unspecified"))
      (node (ref "SW1") (pin "4") (pinfunction "D_4") (pintype "unspecified"))
      (node (ref "SW2") (pin "3") (pinfunction "C_3") (pintype "unspecified"))
      (node (ref "SW2") (pin "4") (pinfunction "D_4") (pintype "unspecified"))
      (node (ref "TF1") (pin "10") (pinfunction "GND_10") (pintype "unspecified"))
      (node (ref "TF1") (pin "11") (pinfunction "GND_11") (pintype "unspecified"))
      (node (ref "TF1") (pin "12") (pinfunction "GND_12") (pintype "unspecified"))
      (node (ref "TF1") (pin "13") (pinfunction "GND_13") (pintype "unspecified"))
      (node (ref "TF1") (pin "6") (pinfunction "VSS_6") (pintype "unspecified"))
      (node (ref "U1") (pin "74") (pinfunction "TVGND_74") (pintype "unspecified"))
      (node (ref "U1") (pin "82") (pinfunction "AGND_82") (pintype "unspecified"))
      (node (ref "U1") (pin "89") (pinfunction "GND_89") (pintype "unspecified"))
      (node (ref "U2") (pin "3") (pinfunction "GND_3") (pintype "unspecified"))
      (node (ref "U3") (pin "3") (pinfunction "IO2_3") (pintype "unspecified"))
      (node (ref "U3") (pin "4") (pinfunction "GND_4") (pintype "unspecified"))
      (node (ref "U4") (pin "5") (pinfunction "GND_5") (pintype "input"))
      (node (ref "U5") (pin "2") (pinfunction "GND_2") (pintype "input"))
      (node (ref "U6") (pin "1") (pinfunction "GND_1") (pintype "input"))
      (node (ref "U7") (pin "1") (pinfunction "VSS_1") (pintype "unspecified"))
      (node (ref "U8") (pin "1") (pinfunction "VSS_1") (pintype "unspecified"))
      (node (ref "U9") (pin "1") (pinfunction "GND_1") (pintype "input"))
      (node (ref "USB1") (pin "1") (pinfunction "GND_1") (pintype "unspecified"))
      (node (ref "USB1") (pin "12") (pinfunction "GND_12") (pintype "unspecified"))
      (node (ref "USB2") (pin "1") (pinfunction "GND_1") (pintype "unspecified"))
      (node (ref "USB2") (pin "12") (pinfunction "GND_12") (pintype "unspecified"))
      (node (ref "X1") (pin "2") (pinfunction "2_2") (pintype "input"))
      (node (ref "X1") (pin "4") (pinfunction "4_4") (pintype "input"))
    )
    (net (code "61") (name "Net-(D1-A)") (class "Default")
      (node (ref "D1") (pin "2") (pinfunction "A_2") (pintype "unspecified"))
      (node (ref "L1") (pin "1") (pinfunction "1_1") (pintype "input"))
      (node (ref "U5") (pin "1") (pinfunction "SW_1") (pintype "input"))
    )
    (net (code "62") (name "Net-(LED1-A)") (class "Default")
      (node (ref "LED1") (pin "2") (pinfunction "A_2") (pintype "input"))
      (node (ref "R5") (pin "2") (pinfunction "2_2") (pintype "input"))
    )
    (net (code "63") (name "Net-(LED2-A)") (class "Default")
      (node (ref "LED2") (pin "2") (pinfunction "A_2") (pintype "input"))
      (node (ref "R6") (pin "2") (pinfunction "2_2") (pintype "input"))
    )
    (net (code "64") (name "Net-(LED3-A)") (class "Default")
      (node (ref "LED3") (pin "2") (pinfunction "A_2") (pintype "input"))
      (node (ref "R7") (pin "2") (pinfunction "2_2") (pintype "input"))
    )
    (net (code "65") (name "Net-(Q1-B)") (class "Default")
      (node (ref "Q1") (pin "1") (pinfunction "B_1") (pintype "unspecified"))
      (node (ref "R26") (pin "1") (pinfunction "1_1") (pintype "input"))
      (node (ref "R27") (pin "1") (pinfunction "1_1") (pintype "input"))
    )
    (net (code "66") (name "Net-(Q1-C)") (class "Default")
      (node (ref "BUZZER1") (pin "2") (pinfunction "2_2") (pintype "input"))
      (node (ref "Q1") (pin "3") (pinfunction "C_3") (pintype "unspecified"))
    )
    (net (code "67") (name "Net-(TF1-CLK)") (class "Default")
      (node (ref "R15") (pin "2") (pinfunction "2_2") (pintype "input"))
      (node (ref "TF1") (pin "5") (pinfunction "CLK_5") (pintype "unspecified"))
    )
    (net (code "68") (name "Net-(U4-VBAT)") (class "Default")
      (node (ref "B1") (pin "1") (pinfunction "1_1") (pintype "input"))
      (node (ref "U4") (pin "6") (pinfunction "VBAT_6") (pintype "input"))
    )
    (net (code "69") (name "Net-(U5-EN)") (class "Default")
      (node (ref "R24") (pin "2") (pinfunction "2_2") (pintype "input"))
      (node (ref "R25") (pin "1") (pinfunction "1_1") (pintype "input"))
      (node (ref "U5") (pin "4") (pinfunction "EN_4") (pintype "input"))
    )
    (net (code "70") (name "Net-(USB1-CC1)") (class "Default")
      (node (ref "R8") (pin "2") (pinfunction "2_2") (pintype "input"))
      (node (ref "USB1") (pin "4") (pinfunction "CC1_4") (pintype "unspecified"))
    )
    (net (code "71") (name "Net-(USB1-CC2)") (class "Default")
      (node (ref "R9") (pin "2") (pinfunction "2_2") (pintype "input"))
      (node (ref "USB1") (pin "10") (pinfunction "CC2_10") (pintype "unspecified"))
    )
    (net (code "72") (name "Net-(USB2-CC1)") (class "Default")
      (node (ref "R10") (pin "2") (pinfunction "2_2") (pintype "input"))
      (node (ref "USB2") (pin "4") (pinfunction "CC1_4") (pintype "unspecified"))
    )
    (net (code "73") (name "Net-(USB2-CC2)") (class "Default")
      (node (ref "R11") (pin "2") (pinfunction "2_2") (pintype "input"))
      (node (ref "USB2") (pin "10") (pinfunction "CC2_10") (pintype "unspecified"))
    )
    (net (code "74") (name "unconnected-(FPC1-Pad35)") (class "Default")
      (node (ref "FPC1") (pin "35") (pinfunction "35_35") (pintype "unspecified+no_connect"))
    )
    (net (code "75") (name "unconnected-(FPC1-Pad37)") (class "Default")
      (node (ref "FPC1") (pin "37") (pinfunction "37_37") (pintype "unspecified+no_connect"))
    )
    (net (code "76") (name "unconnected-(FPC1-Pad38)") (class "Default")
      (node (ref "FPC1") (pin "38") (pinfunction "38_38") (pintype "unspecified+no_connect"))
    )
    (net (code "77") (name "unconnected-(FPC1-Pad39)") (class "Default")
      (node (ref "FPC1") (pin "39") (pinfunction "39_39") (pintype "unspecified+no_connect"))
    )
    (net (code "78") (name "unconnected-(FPC1-Pad40)") (class "Default")
      (node (ref "FPC1") (pin "40") (pinfunction "40_40") (pintype "unspecified+no_connect"))
    )
    (net (code "79") (name "unconnected-(FPC1-Pad41)") (class "Default")
      (node (ref "FPC1") (pin "41") (pinfunction "41_41") (pintype "unspecified+no_connect"))
    )
    (net (code "80") (name "unconnected-(FPC1-Pad42)") (class "Default")
      (node (ref "FPC1") (pin "42") (pinfunction "42_42") (pintype "unspecified+no_connect"))
    )
    (net (code "81") (name "unconnected-(FPC2-Pad7)") (class "Default")
      (node (ref "FPC2") (pin "7") (pinfunction "7_7") (pintype "unspecified+no_connect"))
    )
    (net (code "82") (name "unconnected-(FPC2-Pad8)") (class "Default")
      (node (ref "FPC2") (pin "8") (pinfunction "8_8") (pintype "unspecified+no_connect"))
    )
    (net (code "83") (name "unconnected-(U1-FMINL-Pad84)") (class "Default")
      (node (ref "U1") (pin "84") (pinfunction "FMINL_84") (pintype "unspecified+no_connect"))
    )
    (net (code "84") (name "unconnected-(U1-FMINR-Pad85)") (class "Default")
      (node (ref "U1") (pin "85") (pinfunction "FMINR_85") (pintype "unspecified+no_connect"))
    )
    (net (code "85") (name "unconnected-(U1-HIPCOMFB-Pad2)") (class "Default")
      (node (ref "U1") (pin "2") (pinfunction "HIPCOMFB_2") (pintype "unspecified+no_connect"))
    )
    (net (code "86") (name "unconnected-(U1-HPCOM-Pad3)") (class "Default")
      (node (ref "U1") (pin "3") (pinfunction "HPCOM_3") (pintype "unspecified+no_connect"))
    )
    (net (code "87") (name "unconnected-(U1-HPL-Pad1)") (class "Default")
      (node (ref "U1") (pin "1") (pinfunction "HPL_1") (pintype "unspecified+no_connect"))
    )
    (net (code "88") (name "unconnected-(U1-HPR-Pad88)") (class "Default")
      (node (ref "U1") (pin "88") (pinfunction "HPR_88") (pintype "unspecified+no_connect"))
    )
    (net (code "89") (name "unconnected-(U1-LINL-Pad86)") (class "Default")
      (node (ref "U1") (pin "86") (pinfunction "LINL_86") (pintype "unspecified+no_connect"))
    )
    (net (code "90") (name "unconnected-(U1-LRADC0-Pad79)") (class "Default")
      (node (ref "U1") (pin "79") (pinfunction "LRADC0_79") (pintype "unspecified+no_connect"))
    )
    (net (code "91") (name "unconnected-(U1-MICIN-Pad87)") (class "Default")
      (node (ref "U1") (pin "87") (pinfunction "MICIN_87") (pintype "unspecified+no_connect"))
    )
    (net (code "92") (name "unconnected-(U1-PE3-Pad46)") (class "Default")
      (node (ref "U1") (pin "46") (pinfunction "PE3_46") (pintype "unspecified+no_connect"))
    )
    (net (code "93") (name "unconnected-(U1-PE7-Pad42)") (class "Default")
      (node (ref "U1") (pin "42") (pinfunction "PE7_42") (pintype "unspecified+no_connect"))
    )
    (net (code "94") (name "unconnected-(U1-PE8-Pad41)") (class "Default")
      (node (ref "U1") (pin "41") (pinfunction "PE8_41") (pintype "unspecified+no_connect"))
    )
    (net (code "95") (name "unconnected-(U1-TPX1-Pad66)") (class "Default")
      (node (ref "U1") (pin "66") (pinfunction "TPX1_66") (pintype "unspecified+no_connect"))
    )
    (net (code "96") (name "unconnected-(U1-TPX2-Pad65)") (class "Default")
      (node (ref "U1") (pin "65") (pinfunction "TPX2_65") (pintype "unspecified+no_connect"))
    )
    (net (code "97") (name "unconnected-(U1-TVIN0-Pad78)") (class "Default")
      (node (ref "U1") (pin "78") (pinfunction "TVIN0_78") (pintype "unspecified+no_connect"))
    )
    (net (code "98") (name "unconnected-(U1-TVIN1-Pad77)") (class "Default")
      (node (ref "U1") (pin "77") (pinfunction "TVIN1_77") (pintype "unspecified+no_connect"))
    )
    (net (code "99") (name "unconnected-(U1-TVOUT-Pad72)") (class "Default")
      (node (ref "U1") (pin "72") (pinfunction "TVOUT_72") (pintype "unspecified+no_connect"))
    )
    (net (code "100") (name "unconnected-(U1-TV_VRN-Pad75)") (class "Default")
      (node (ref "U1") (pin "75") (pinfunction "TV_VRN_75") (pintype "unspecified+no_connect"))
    )
    (net (code "101") (name "unconnected-(U1-TV_VRP-Pad76)") (class "Default")
      (node (ref "U1") (pin "76") (pinfunction "TV_VRP_76") (pintype "unspecified+no_connect"))
    )
    (net (code "102") (name "unconnected-(U1-VRA1-Pad81)") (class "Default")
      (node (ref "U1") (pin "81") (pinfunction "VRA1_81") (pintype "unspecified+no_connect"))
    )
    (net (code "103") (name "unconnected-(U1-VRA2-Pad83)") (class "Default")
      (node (ref "U1") (pin "83") (pinfunction "VRA2_83") (pintype "unspecified+no_connect"))
    )
    (net (code "104") (name "unconnected-(U2-RTS#-Pad4)") (class "Default")
      (node (ref "U2") (pin "4") (pinfunction "RTS#_4") (pintype "unspecified+no_connect"))
    )
    (net (code "105") (name "unconnected-(U4-F32K-Pad1)") (class "Default")
      (node (ref "U4") (pin "1") (pinfunction "F32K_1") (pintype "input+no_connect"))
    )
    (net (code "106") (name "unconnected-(U4-INT-Pad3)") (class "Default")
      (node (ref "U4") (pin "3") (pinfunction "INT_3") (pintype "input+no_connect"))
    )
    (net (code "107") (name "unconnected-(U4-NC-Pad4)") (class "Default")
      (node (ref "U4") (pin "4") (pinfunction "NC_4") (pintype "input+no_connect"))
    )
    (net (code "108") (name "unconnected-(USB1-SBU1-Pad9)") (class "Default")
      (node (ref "USB1") (pin "9") (pinfunction "SBU1_9") (pintype "unspecified+no_connect"))
    )
    (net (code "109") (name "unconnected-(USB1-SBU2-Pad3)") (class "Default")
      (node (ref "USB1") (pin "3") (pinfunction "SBU2_3") (pintype "unspecified+no_connect"))
    )
    (net (code "110") (name "unconnected-(USB1-SHELL-Pad13)") (class "Default")
      (node (ref "USB1") (pin "13") (pinfunction "SHELL_13") (pintype "unspecified+no_connect"))
    )
    (net (code "111") (name "unconnected-(USB1-SHELL-Pad14)") (class "Default")
      (node (ref "USB1") (pin "14") (pinfunction "SHELL_14") (pintype "unspecified+no_connect"))
    )
    (net (code "112") (name "unconnected-(USB2-SBU1-Pad9)") (class "Default")
      (node (ref "USB2") (pin "9") (pinfunction "SBU1_9") (pintype "unspecified+no_connect"))
    )
    (net (code "113") (name "unconnected-(USB2-SBU2-Pad3)") (class "Default")
      (node (ref "USB2") (pin "3") (pinfunction "SBU2_3") (pintype "unspecified+no_connect"))
    )
    (net (code "114") (name "unconnected-(USB2-SHELL-Pad13)") (class "Default")
      (node (ref "USB2") (pin "13") (pinfunction "SHELL_13") (pintype "unspecified+no_connect"))
    )
    (net (code "115") (name "unconnected-(USB2-SHELL-Pad14)") (class "Default")
      (node (ref "USB2") (pin "14") (pinfunction "SHELL_14") (pintype "unspecified+no_connect"))
    )
  )
)
